# AltiumSTM32_Schematic.net
KiCad netlist of a schematic drawn in Altium Designer
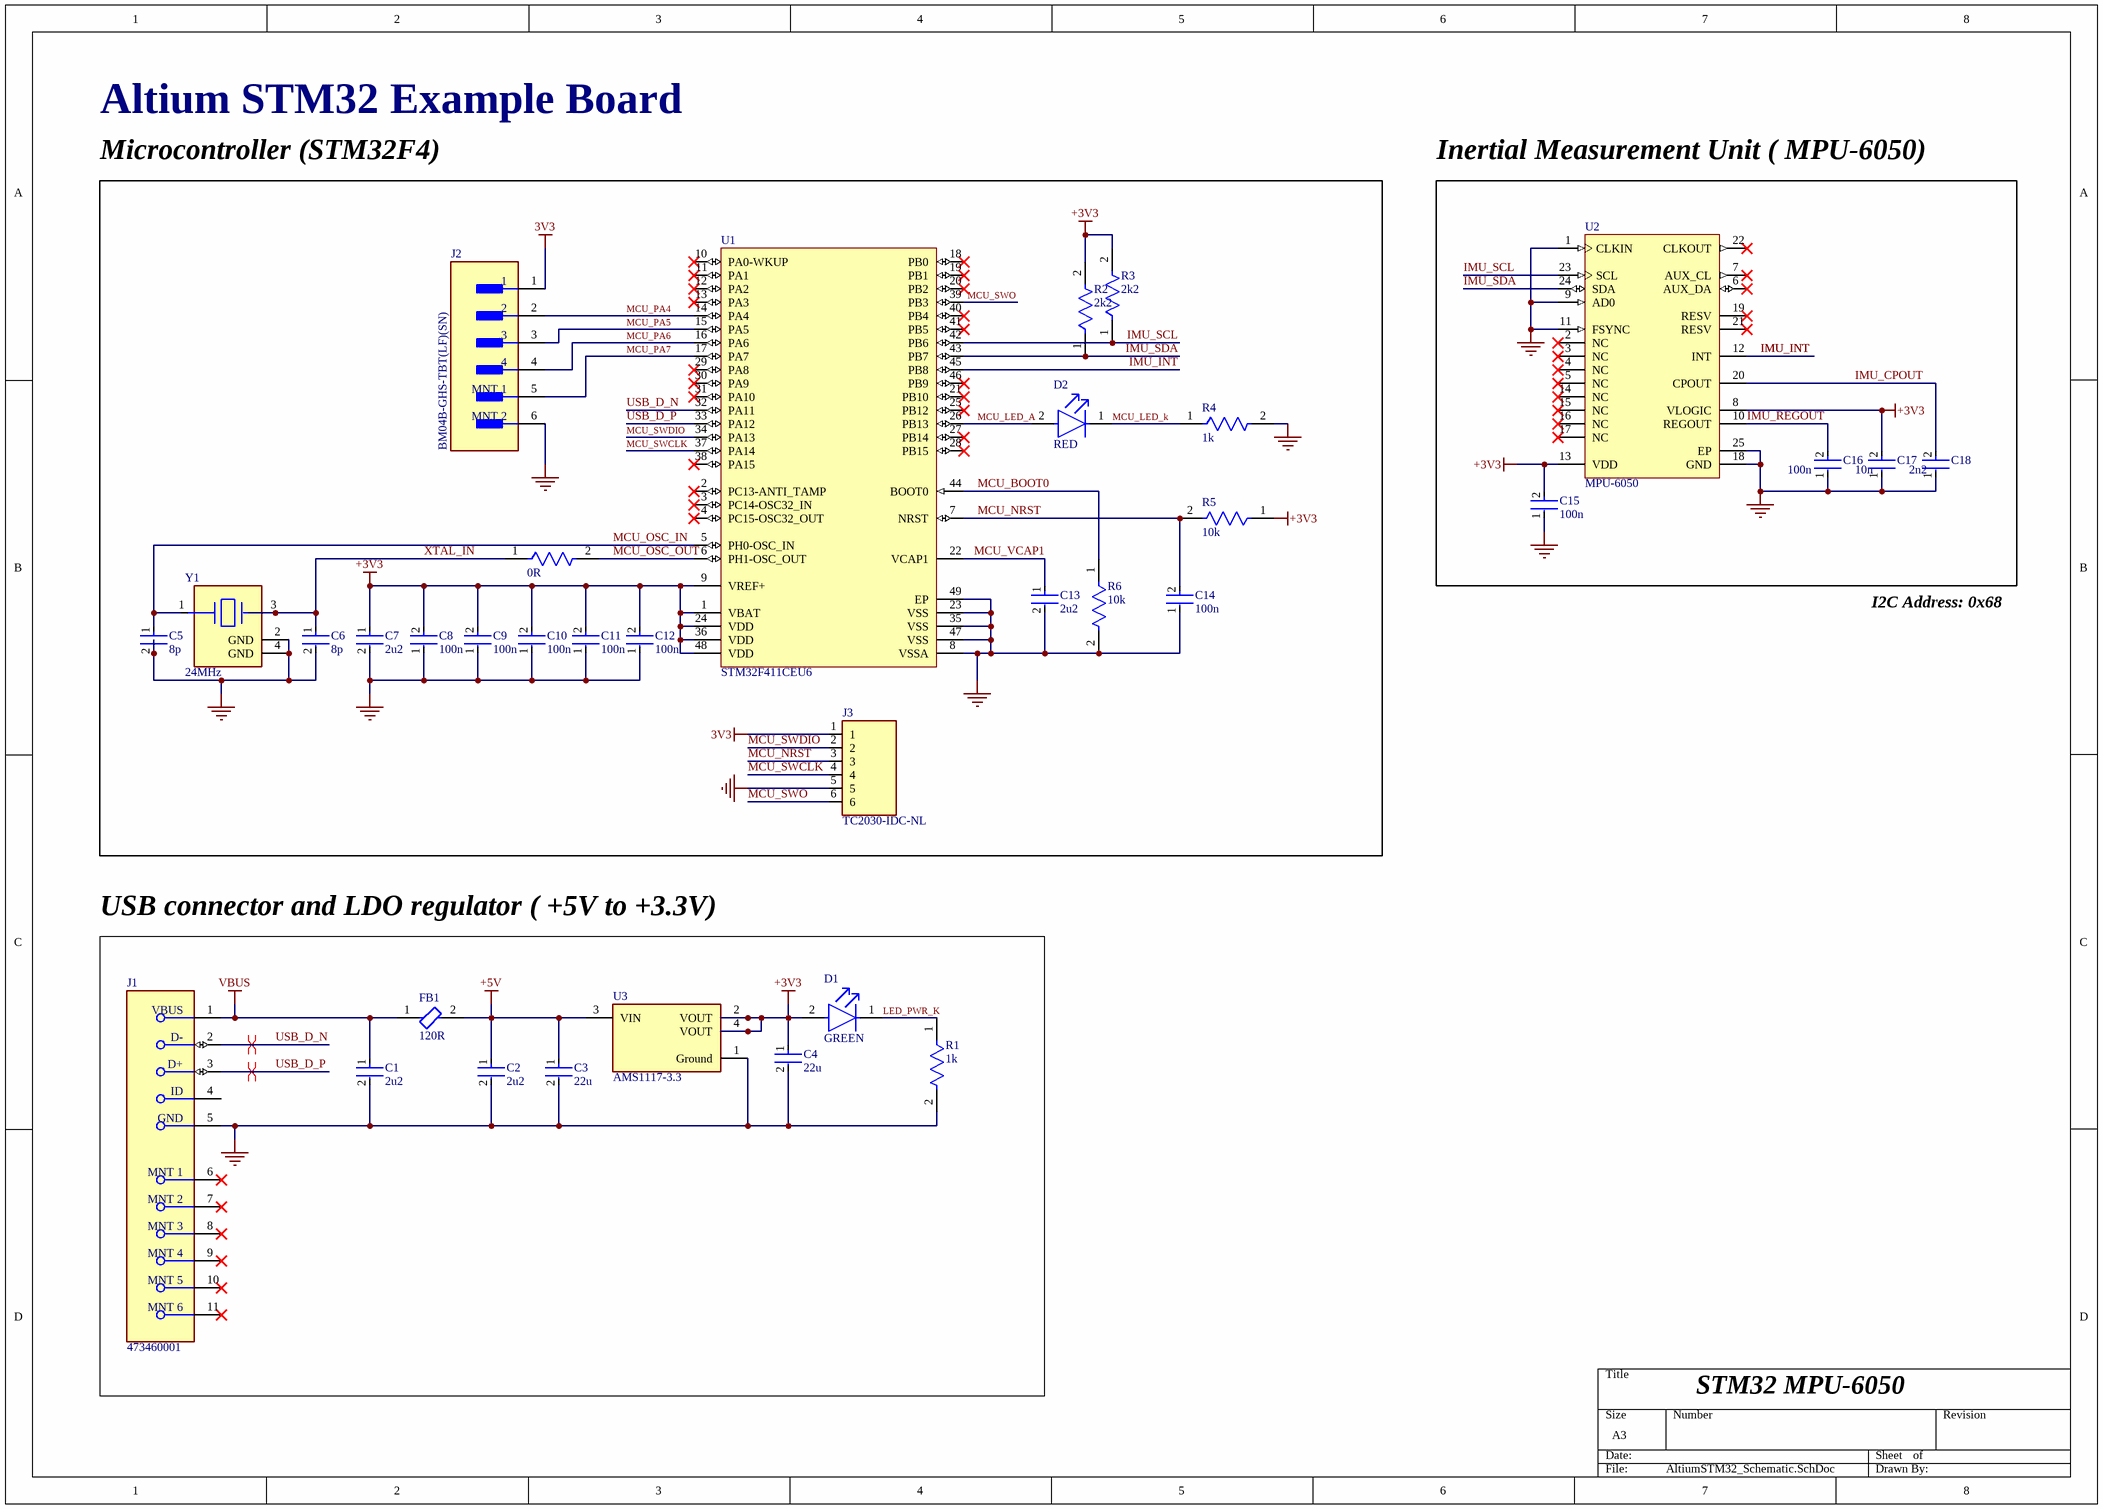
[diagram p0: AltiumSTM32_Schematic.SchDoc]

(export (version "E")
  (design (tool "Eeschema 10.0.6"))
  (components
    (comp (ref "C1")
      (value "2u2")
      (footprint "FP-CC0603-DA-MFG")
      (description "CAP CER 2.2UF 16V X7R 0603")
      (fields (field (name "VOLTAGE") "16 V") (field (name "MANUFACTURER") "YAGEO"))
      (libsource (lib "Altium Content Vault") (part "11868f565c42a9108669ba33697ecf6"))
    )
    (comp (ref "C2")
      (value "2u2")
      (footprint "FP-CC0603-DA-MFG")
      (description "CAP CER 2.2UF 16V X7R 0603")
      (fields (field (name "VOLTAGE") "16 V") (field (name "MANUFACTURER") "YAGEO"))
      (libsource (lib "Altium Content Vault") (part "11868f565c42a9108669ba33697ecf6"))
    )
    (comp (ref "C3")
      (value "22u")
      (footprint "FP-GRT21B-0_2-MFG")
      (description "Multi-Layer Ceramic Capacitor 22uF 16V X5R ±20% 0805 Emboss T/R")
      (fields (field (name "TOLERANCE") "20%"))
      (libsource (lib "Altium Content Vault") (part "02cd4be3c70576c341d710602a673aa"))
    )
    (comp (ref "C4")
      (value "22u")
      (footprint "FP-GRT21B-0_2-MFG")
      (description "Multi-Layer Ceramic Capacitor 22uF 16V X5R ±20% 0805 Emboss T/R")
      (fields (field (name "TOLERANCE") "20%"))
      (libsource (lib "Altium Content Vault") (part "02cd4be3c70576c341d710602a673aa"))
    )
    (comp (ref "C5")
      (value "8p")
      (footprint "FP-CC0402-MFG")
      (description "CAP CER 8PF 50V NPO 0402")
      (fields
        (field (name "TOLERANCE") "0.1pF")
        (field (name "MANUFACTURER PART NUMBER") "CC0402BRNPO9BN8R0")
      )
      (libsource (lib "Altium Content Vault") (part "11868f565c42a9108669ba33697ecf6"))
    )
    (comp (ref "C6")
      (value "8p")
      (footprint "FP-CC0402-MFG")
      (description "CAP CER 8PF 50V NPO 0402")
      (fields
        (field (name "TOLERANCE") "0.1pF")
        (field (name "MANUFACTURER PART NUMBER") "CC0402BRNPO9BN8R0")
      )
      (libsource (lib "Altium Content Vault") (part "11868f565c42a9108669ba33697ecf6"))
    )
    (comp (ref "C7")
      (value "2u2")
      (footprint "FP-CC0603-DA-MFG")
      (description "CAP CER 2.2UF 16V X7R 0603")
      (fields (field (name "VOLTAGE") "16 V") (field (name "MANUFACTURER") "YAGEO"))
      (libsource (lib "Altium Content Vault") (part "11868f565c42a9108669ba33697ecf6"))
    )
    (comp (ref "C8")
      (value "100n")
      (footprint "FP-CC0402-0_05-0_55-L2_0-MFG")
      (description "CAP CER 0.1UF 16V X7R 0402")
      (fields (field (name "TOLERANCE") "5%"))
      (libsource (lib "Altium Content Vault") (part "236180d848d6139a670b325ea6854c9"))
    )
    (comp (ref "C9")
      (value "100n")
      (footprint "FP-CC0402-0_05-0_55-L2_0-MFG")
      (description "CAP CER 0.1UF 16V X7R 0402")
      (fields (field (name "TOLERANCE") "5%"))
      (libsource (lib "Altium Content Vault") (part "236180d848d6139a670b325ea6854c9"))
    )
    (comp (ref "C10")
      (value "100n")
      (footprint "FP-CC0402-0_05-0_55-L2_0-MFG")
      (description "CAP CER 0.1UF 16V X7R 0402")
      (fields (field (name "TOLERANCE") "5%"))
      (libsource (lib "Altium Content Vault") (part "236180d848d6139a670b325ea6854c9"))
    )
    (comp (ref "C11")
      (value "100n")
      (footprint "FP-CC0402-0_05-0_55-L2_0-MFG")
      (description "CAP CER 0.1UF 16V X7R 0402")
      (fields (field (name "TOLERANCE") "5%"))
      (libsource (lib "Altium Content Vault") (part "236180d848d6139a670b325ea6854c9"))
    )
    (comp (ref "C12")
      (value "100n")
      (footprint "FP-CC0402-0_05-0_55-L2_0-MFG")
      (description "CAP CER 0.1UF 16V X7R 0402")
      (fields (field (name "TOLERANCE") "5%"))
      (libsource (lib "Altium Content Vault") (part "236180d848d6139a670b325ea6854c9"))
    )
    (comp (ref "C13")
      (value "2u2")
      (footprint "FP-CC0603-DA-MFG")
      (description "CAP CER 2.2UF 16V X7R 0603")
      (fields (field (name "VOLTAGE") "16 V") (field (name "MANUFACTURER") "YAGEO"))
      (libsource (lib "Altium Content Vault") (part "11868f565c42a9108669ba33697ecf6"))
    )
    (comp (ref "C14")
      (value "100n")
      (footprint "FP-CC0402-0_05-0_55-L2_0-MFG")
      (description "CAP CER 0.1UF 16V X7R 0402")
      (fields (field (name "TOLERANCE") "5%"))
      (libsource (lib "Altium Content Vault") (part "236180d848d6139a670b325ea6854c9"))
    )
    (comp (ref "C15")
      (value "100n")
      (footprint "FP-CC0402-0_05-0_55-L2_0-MFG")
      (description "CAP CER 0.1UF 16V X7R 0402")
      (fields (field (name "TOLERANCE") "5%"))
      (libsource (lib "Altium Content Vault") (part "236180d848d6139a670b325ea6854c9"))
    )
    (comp (ref "C16")
      (value "100n")
      (footprint "FP-CC0402-0_05-0_55-L2_0-MFG")
      (description "CAP CER 0.1UF 16V X7R 0402")
      (fields (field (name "TOLERANCE") "5%"))
      (libsource (lib "Altium Content Vault") (part "236180d848d6139a670b325ea6854c9"))
    )
    (comp (ref "C17")
      (value "10n")
      (footprint "FP-CC0402-0_05-0_55-L2_0-MFG")
      (description "CAP CER 0.1UF 16V X7R 0402")
      (fields (field (name "TOLERANCE") "5%"))
      (libsource (lib "Altium Content Vault") (part "236180d848d6139a670b325ea6854c9"))
    )
    (comp (ref "C18")
      (value "2n2")
      (footprint "FP-CC0402-0_05-0_55-L2_0-MFG")
      (description "CAP CER 0.1UF 16V X7R 0402")
      (fields (field (name "TOLERANCE") "5%"))
      (libsource (lib "Altium Content Vault") (part "236180d848d6139a670b325ea6854c9"))
    )
    (comp (ref "D1")
      (value "GREEN")
      (footprint "FP-SML-P1-MFG")
      (description "LED GREEN CLEAR 1006 SMD")
      (fields (field (name "MANUFACTURER PART NUMBER") "SML-P13PTT86R") (field (name "MANUFACTURER") "Rohm"))
      (libsource (lib "Altium Content Vault") (part "8706943c75ba83719d021d2fdc84c58"))
    )
    (comp (ref "D2")
      (value "RED")
      (footprint "FP-SML-P1-MFG")
      (description "LED RED CLEAR 0402 SMD")
      (fields
        (field (name "OCTOPART") "https://octopart.com/sml-p12vtt86r-rohm-34112315")
        (field (name "MANUFACTURER") "Rohm")
      )
      (libsource (lib "Altium Content Vault") (part "8706943c75ba83719d021d2fdc84c58"))
    )
    (comp (ref "FB1")
      (value "120R")
      (footprint "FP-MPZ1608-0_6-IPC_A")
      (description "FERRITE BEAD 120 OHM 0603 1LN")
      (fields (field (name "TOLERANCE") "25%"))
      (libsource (lib "Altium Content Vault") (part "5f30dd21d616792df468990f7003faa"))
    )
    (comp (ref "J1")
      (value "473460001")
      (footprint "FP-473460001-MFG")
      (description "CONN RCPT USB2.0 MICRO B SMD R/A")
      (fields
        (field (name "OCTOPART") "https://octopart.com/47346-0001-molex-7164928")
        (field (name "MANUFACTURER") "Molex")
      )
      (libsource (lib "Altium Content Vault") (part "53ae1f1d9b557310b43ca686e5bb76a"))
    )
    (comp (ref "J2")
      (value "BM04B-GHS-TBT(LF)(SN)")
      (footprint "FP-BM04B-GHS-TBT_LF_SN-MFG")
      (description "CONN HEADER SMD 4POS 1.25MM")
      (libsource (lib "Altium Content Vault") (part "8e3688c4b118bffc0dd9b7401e414ba"))
    )
    (comp (ref "J3")
      (value "TC2030-IDC-NL")
      (footprint "TC2030-IDC-NL")
      (description "CABLE ADAPTER 6 POS")
      (libsource (lib "AltiumSTM32_PCB") (part "CMP-003-000003-1"))
    )
    (comp (ref "R1")
      (value "1k")
      (footprint "FP-CRGCQ0402-IPC_C")
      (description "CRGCQ 0402 10K 1%")
      (fields (field (name "TOLERANCE") "0.01") (field (name "MANUFACTURER") "TE Connectivity"))
      (libsource (lib "Altium Content Vault") (part "1029c3af85768c4190bb7ad29bc67b5"))
    )
    (comp (ref "R2")
      (value "2k2")
      (footprint "FP-CRGCQ0402-IPC_C")
      (description "CRGCQ 0402 10K 1%")
      (fields (field (name "TOLERANCE") "0.01") (field (name "MANUFACTURER") "TE Connectivity"))
      (libsource (lib "Altium Content Vault") (part "1029c3af85768c4190bb7ad29bc67b5"))
    )
    (comp (ref "R3")
      (value "2k2")
      (footprint "FP-CRGCQ0402-IPC_C")
      (description "CRGCQ 0402 10K 1%")
      (fields (field (name "TOLERANCE") "0.01") (field (name "MANUFACTURER") "TE Connectivity"))
      (libsource (lib "Altium Content Vault") (part "1029c3af85768c4190bb7ad29bc67b5"))
    )
    (comp (ref "R4")
      (value "1k")
      (footprint "FP-CRGCQ0402-IPC_C")
      (description "CRGCQ 0402 10K 1%")
      (fields (field (name "TOLERANCE") "0.01") (field (name "MANUFACTURER") "TE Connectivity"))
      (libsource (lib "Altium Content Vault") (part "1029c3af85768c4190bb7ad29bc67b5"))
    )
    (comp (ref "R5")
      (value "10k")
      (footprint "FP-CRGCQ0402-IPC_C")
      (description "CRGCQ 0402 10K 1%")
      (fields (field (name "TOLERANCE") "0.01") (field (name "MANUFACTURER") "TE Connectivity"))
      (libsource (lib "Altium Content Vault") (part "1029c3af85768c4190bb7ad29bc67b5"))
    )
    (comp (ref "R6")
      (value "10k")
      (footprint "FP-CRGCQ0402-IPC_C")
      (description "CRGCQ 0402 10K 1%")
      (fields (field (name "TOLERANCE") "0.01") (field (name "MANUFACTURER") "TE Connectivity"))
      (libsource (lib "Altium Content Vault") (part "1029c3af85768c4190bb7ad29bc67b5"))
    )
    (comp (ref "R7")
      (value "0R")
      (footprint "FP-CRGCQ0402-IPC_C")
      (description "CRGCQ 0402 10K 1%")
      (fields (field (name "TOLERANCE") "0.01") (field (name "MANUFACTURER") "TE Connectivity"))
      (libsource (lib "Altium Content Vault") (part "1029c3af85768c4190bb7ad29bc67b5"))
    )
    (comp (ref "U1")
      (value "STM32F411CEU6")
      (footprint "STM-UFQFPN48_L")
      (libsource (lib "Altium Content Vault") (part "MC-ARM-STM32F411-UFQFPN48"))
    )
    (comp (ref "U2")
      (value "MPU-6050")
      (footprint "IS-QFN-24_V")
      (fields (field (name "MANUFACTURER") "InvenSense"))
      (libsource (lib "Altium Content Vault") (part "IS-MPU-6050-QFN-24"))
    )
    (comp (ref "U3")
      (value "AMS1117-3.3")
      (footprint "FP-AMS1117-IPC_C")
      (description "LDO Voltage Regulators 1A, 3.3V")
      (fields
        (field (name "OCTOPART") "https://octopart.com/ams1117-3.3-advanced+monolithic+systems-25899300")
        (field (name "MANUFACTURER") "Advanced Monolithic Systems")
      )
      (libsource (lib "Altium Content Vault") (part "8bdbb5f8e77002000e30dd2845d0354"))
    )
    (comp (ref "Y1")
      (value "24MHz")
      (footprint "FP-TSX-3225-MFG")
      (description "CRYSTAL 24.0000MHZ 9PF SMD")
      (fields (field (name "TOLERANCE") "10ppm"))
      (libsource (lib "Altium Content Vault") (part "862d5228ea4a4c8f16e8fb874e464c7"))
    )
  )
  (nets
    (net (code "1") (name "+3V3") (class "Default")
      (node (ref "C10") (pin "2") (pinfunction "2_2") (pintype "passive"))
      (node (ref "C11") (pin "2") (pinfunction "2_2") (pintype "passive"))
      (node (ref "C12") (pin "2") (pinfunction "2_2") (pintype "passive"))
      (node (ref "C15") (pin "2") (pinfunction "2_2") (pintype "passive"))
      (node (ref "C17") (pin "2") (pinfunction "2_2") (pintype "passive"))
      (node (ref "C4") (pin "1") (pinfunction "1_1") (pintype "passive"))
      (node (ref "C7") (pin "1") (pinfunction "1_1") (pintype "passive"))
      (node (ref "C8") (pin "2") (pinfunction "2_2") (pintype "passive"))
      (node (ref "C9") (pin "2") (pinfunction "2_2") (pintype "passive"))
      (node (ref "D1") (pin "2") (pinfunction "A_2") (pintype "passive"))
      (node (ref "R2") (pin "2") (pinfunction "2_2") (pintype "passive"))
      (node (ref "R3") (pin "2") (pinfunction "2_2") (pintype "passive"))
      (node (ref "R5") (pin "1") (pinfunction "1_1") (pintype "passive"))
      (node (ref "U1") (pin "1") (pinfunction "VBAT_1") (pintype "power_in"))
      (node (ref "U1") (pin "24") (pinfunction "VDD_24") (pintype "power_in"))
      (node (ref "U1") (pin "36") (pinfunction "VDD_36") (pintype "power_in"))
      (node (ref "U1") (pin "48") (pinfunction "VDD_48") (pintype "power_in"))
      (node (ref "U1") (pin "9") (pinfunction "VREF+_9") (pintype "power_in"))
      (node (ref "U2") (pin "13") (pinfunction "VDD_13") (pintype "power_in"))
      (node (ref "U2") (pin "8") (pinfunction "VLOGIC_8") (pintype "power_in"))
      (node (ref "U3") (pin "2") (pinfunction "VOUT_2") (pintype "passive"))
      (node (ref "U3") (pin "4") (pinfunction "VOUT_4") (pintype "passive"))
    )
    (net (code "2") (name "+5V") (class "Default")
      (node (ref "C2") (pin "1") (pinfunction "1_1") (pintype "passive"))
      (node (ref "C3") (pin "1") (pinfunction "1_1") (pintype "passive"))
      (node (ref "FB1") (pin "2") (pinfunction "2_2") (pintype "passive"))
      (node (ref "U3") (pin "3") (pinfunction "VIN_3") (pintype "power_in"))
    )
    (net (code "3") (name "/IMU_CPOUT") (class "Default")
      (node (ref "C18") (pin "2") (pinfunction "2_2") (pintype "passive"))
      (node (ref "U2") (pin "20") (pinfunction "CPOUT_20") (pintype "passive"))
    )
    (net (code "4") (name "/IMU_INT") (class "Default")
      (node (ref "U1") (pin "45") (pinfunction "PB8_45") (pintype "bidirectional"))
      (node (ref "U2") (pin "12") (pinfunction "INT_12") (pintype "open_collector"))
    )
    (net (code "5") (name "/IMU_REGOUT") (class "Default")
      (node (ref "C16") (pin "2") (pinfunction "2_2") (pintype "passive"))
      (node (ref "U2") (pin "10") (pinfunction "REGOUT_10") (pintype "passive"))
    )
    (net (code "6") (name "/IMU_SCL") (class "Default")
      (node (ref "R3") (pin "1") (pinfunction "1_1") (pintype "passive"))
      (node (ref "U1") (pin "42") (pinfunction "PB6_42") (pintype "bidirectional"))
      (node (ref "U2") (pin "23") (pinfunction "SCL_23") (pintype "input"))
    )
    (net (code "7") (name "/IMU_SDA") (class "Default")
      (node (ref "R2") (pin "1") (pinfunction "1_1") (pintype "passive"))
      (node (ref "U1") (pin "43") (pinfunction "PB7_43") (pintype "bidirectional"))
      (node (ref "U2") (pin "24") (pinfunction "SDA_24") (pintype "bidirectional"))
    )
    (net (code "8") (name "/LED_PWR_K") (class "Default")
      (node (ref "D1") (pin "1") (pinfunction "C_1") (pintype "passive"))
      (node (ref "R1") (pin "1") (pinfunction "1_1") (pintype "passive"))
    )
    (net (code "9") (name "/MCU_BOOT0") (class "Default")
      (node (ref "R6") (pin "1") (pinfunction "1_1") (pintype "passive"))
      (node (ref "U1") (pin "44") (pinfunction "BOOT0_44") (pintype "input"))
    )
    (net (code "10") (name "/MCU_LED_A") (class "Default")
      (node (ref "D2") (pin "2") (pinfunction "A_2") (pintype "passive"))
      (node (ref "U1") (pin "26") (pinfunction "PB13_26") (pintype "bidirectional"))
    )
    (net (code "11") (name "/MCU_LED_k") (class "Default")
      (node (ref "D2") (pin "1") (pinfunction "C_1") (pintype "passive"))
      (node (ref "R4") (pin "1") (pinfunction "1_1") (pintype "passive"))
    )
    (net (code "12") (name "/MCU_NRST") (class "Default")
      (node (ref "C14") (pin "2") (pinfunction "2_2") (pintype "passive"))
      (node (ref "J3") (pin "3") (pinfunction "3_3") (pintype "passive"))
      (node (ref "R5") (pin "2") (pinfunction "2_2") (pintype "passive"))
      (node (ref "U1") (pin "7") (pinfunction "NRST_7") (pintype "bidirectional"))
    )
    (net (code "13") (name "/MCU_OSC_IN") (class "Default")
      (node (ref "C5") (pin "1") (pinfunction "1_1") (pintype "passive"))
      (node (ref "U1") (pin "5") (pinfunction "PH0-OSC_IN_5") (pintype "bidirectional"))
      (node (ref "Y1") (pin "1") (pinfunction "1_1") (pintype "passive"))
    )
    (net (code "14") (name "/MCU_OSC_OUT") (class "Default")
      (node (ref "R7") (pin "2") (pinfunction "2_2") (pintype "passive"))
      (node (ref "U1") (pin "6") (pinfunction "PH1-OSC_OUT_6") (pintype "bidirectional"))
    )
    (net (code "15") (name "/MCU_PA4") (class "Default")
      (node (ref "J2") (pin "2") (pinfunction "2_2") (pintype "passive"))
      (node (ref "U1") (pin "14") (pinfunction "PA4_14") (pintype "bidirectional"))
    )
    (net (code "16") (name "/MCU_PA5") (class "Default")
      (node (ref "J2") (pin "3") (pinfunction "3_3") (pintype "passive"))
      (node (ref "U1") (pin "15") (pinfunction "PA5_15") (pintype "bidirectional"))
    )
    (net (code "17") (name "/MCU_PA6") (class "Default")
      (node (ref "J2") (pin "4") (pinfunction "4_4") (pintype "passive"))
      (node (ref "U1") (pin "16") (pinfunction "PA6_16") (pintype "bidirectional"))
    )
    (net (code "18") (name "/MCU_PA7") (class "Default")
      (node (ref "J2") (pin "5") (pinfunction "MNT_1_5") (pintype "passive"))
      (node (ref "U1") (pin "17") (pinfunction "PA7_17") (pintype "bidirectional"))
    )
    (net (code "19") (name "/MCU_SWCLK") (class "Default")
      (node (ref "J3") (pin "4") (pinfunction "4_4") (pintype "passive"))
      (node (ref "U1") (pin "37") (pinfunction "PA14_37") (pintype "bidirectional"))
    )
    (net (code "20") (name "/MCU_SWDIO") (class "Default")
      (node (ref "J3") (pin "2") (pinfunction "2_2") (pintype "passive"))
      (node (ref "U1") (pin "34") (pinfunction "PA13_34") (pintype "bidirectional"))
    )
    (net (code "21") (name "/MCU_SWO") (class "Default")
      (node (ref "J3") (pin "6") (pinfunction "6_6") (pintype "passive"))
      (node (ref "U1") (pin "39") (pinfunction "PB3_39") (pintype "bidirectional"))
    )
    (net (code "22") (name "/MCU_VCAP1") (class "Default")
      (node (ref "C13") (pin "1") (pinfunction "1_1") (pintype "passive"))
      (node (ref "U1") (pin "22") (pinfunction "VCAP1_22") (pintype "passive"))
    )
    (net (code "23") (name "/USB_D_N") (class "Default")
      (node (ref "J1") (pin "2") (pinfunction "D-_2") (pintype "bidirectional"))
      (node (ref "U1") (pin "32") (pinfunction "PA11_32") (pintype "bidirectional"))
    )
    (net (code "24") (name "/USB_D_P") (class "Default")
      (node (ref "J1") (pin "3") (pinfunction "D+_3") (pintype "bidirectional"))
      (node (ref "U1") (pin "33") (pinfunction "PA12_33") (pintype "bidirectional"))
    )
    (net (code "25") (name "/XTAL_IN") (class "Default")
      (node (ref "C6") (pin "1") (pinfunction "1_1") (pintype "passive"))
      (node (ref "R7") (pin "1") (pinfunction "1_1") (pintype "passive"))
      (node (ref "Y1") (pin "3") (pinfunction "3_3") (pintype "passive"))
    )
    (net (code "26") (name "3V3") (class "Default")
      (node (ref "J2") (pin "1") (pinfunction "1_1") (pintype "passive"))
      (node (ref "J3") (pin "1") (pinfunction "1_1") (pintype "passive"))
    )
    (net (code "27") (name "GND") (class "Default")
      (node (ref "C1") (pin "2") (pinfunction "2_2") (pintype "passive"))
      (node (ref "C10") (pin "1") (pinfunction "1_1") (pintype "passive"))
      (node (ref "C11") (pin "1") (pinfunction "1_1") (pintype "passive"))
      (node (ref "C12") (pin "1") (pinfunction "1_1") (pintype "passive"))
      (node (ref "C13") (pin "2") (pinfunction "2_2") (pintype "passive"))
      (node (ref "C14") (pin "1") (pinfunction "1_1") (pintype "passive"))
      (node (ref "C15") (pin "1") (pinfunction "1_1") (pintype "passive"))
      (node (ref "C16") (pin "1") (pinfunction "1_1") (pintype "passive"))
      (node (ref "C17") (pin "1") (pinfunction "1_1") (pintype "passive"))
      (node (ref "C18") (pin "1") (pinfunction "1_1") (pintype "passive"))
      (node (ref "C2") (pin "2") (pinfunction "2_2") (pintype "passive"))
      (node (ref "C3") (pin "2") (pinfunction "2_2") (pintype "passive"))
      (node (ref "C4") (pin "2") (pinfunction "2_2") (pintype "passive"))
      (node (ref "C5") (pin "2") (pinfunction "2_2") (pintype "passive"))
      (node (ref "C6") (pin "2") (pinfunction "2_2") (pintype "passive"))
      (node (ref "C7") (pin "2") (pinfunction "2_2") (pintype "passive"))
      (node (ref "C8") (pin "1") (pinfunction "1_1") (pintype "passive"))
      (node (ref "C9") (pin "1") (pinfunction "1_1") (pintype "passive"))
      (node (ref "J1") (pin "5") (pinfunction "GND_5") (pintype "power_in"))
      (node (ref "J2") (pin "6") (pinfunction "MNT_2_6") (pintype "passive"))
      (node (ref "J3") (pin "5") (pinfunction "5_5") (pintype "passive"))
      (node (ref "R1") (pin "2") (pinfunction "2_2") (pintype "passive"))
      (node (ref "R4") (pin "2") (pinfunction "2_2") (pintype "passive"))
      (node (ref "R6") (pin "2") (pinfunction "2_2") (pintype "passive"))
      (node (ref "U1") (pin "23") (pinfunction "VSS_23") (pintype "power_in"))
      (node (ref "U1") (pin "35") (pinfunction "VSS_35") (pintype "power_in"))
      (node (ref "U1") (pin "47") (pinfunction "VSS_47") (pintype "power_in"))
      (node (ref "U1") (pin "49") (pinfunction "EP_49") (pintype "power_in"))
      (node (ref "U1") (pin "8") (pinfunction "VSSA_8") (pintype "power_in"))
      (node (ref "U2") (pin "1") (pinfunction "CLKIN_1") (pintype "input"))
      (node (ref "U2") (pin "11") (pinfunction "FSYNC_11") (pintype "input"))
      (node (ref "U2") (pin "18") (pinfunction "GND_18") (pintype "power_in"))
      (node (ref "U2") (pin "25") (pinfunction "EP_25") (pintype "power_in"))
      (node (ref "U2") (pin "9") (pinfunction "AD0_9") (pintype "input"))
      (node (ref "U3") (pin "1") (pinfunction "Ground_1") (pintype "power_in"))
      (node (ref "Y1") (pin "2") (pinfunction "GND_2") (pintype "power_in"))
      (node (ref "Y1") (pin "4") (pinfunction "GND_4") (pintype "power_in"))
    )
    (net (code "28") (name "VBUS") (class "Default")
      (node (ref "C1") (pin "1") (pinfunction "1_1") (pintype "passive"))
      (node (ref "FB1") (pin "1") (pinfunction "1_1") (pintype "passive"))
      (node (ref "J1") (pin "1") (pinfunction "VBUS_1") (pintype "power_in"))
    )
    (net (code "29") (name "unconnected-(J1-ID-Pad4)") (class "Default")
      (node (ref "J1") (pin "4") (pinfunction "ID_4") (pintype "passive"))
    )
    (net (code "30") (name "unconnected-(J1-MNT_1-Pad6)") (class "Default")
      (node (ref "J1") (pin "6") (pinfunction "MNT_1_6") (pintype "passive+no_connect"))
    )
    (net (code "31") (name "unconnected-(J1-MNT_2-Pad7)") (class "Default")
      (node (ref "J1") (pin "7") (pinfunction "MNT_2_7") (pintype "passive+no_connect"))
    )
    (net (code "32") (name "unconnected-(J1-MNT_3-Pad8)") (class "Default")
      (node (ref "J1") (pin "8") (pinfunction "MNT_3_8") (pintype "passive+no_connect"))
    )
    (net (code "33") (name "unconnected-(J1-MNT_4-Pad9)") (class "Default")
      (node (ref "J1") (pin "9") (pinfunction "MNT_4_9") (pintype "passive+no_connect"))
    )
    (net (code "34") (name "unconnected-(J1-MNT_5-Pad10)") (class "Default")
      (node (ref "J1") (pin "10") (pinfunction "MNT_5_10") (pintype "passive+no_connect"))
    )
    (net (code "35") (name "unconnected-(J1-MNT_6-Pad11)") (class "Default")
      (node (ref "J1") (pin "11") (pinfunction "MNT_6_11") (pintype "passive+no_connect"))
    )
    (net (code "36") (name "unconnected-(U1-PA0-WKUP-Pad10)") (class "Default")
      (node (ref "U1") (pin "10") (pinfunction "PA0-WKUP_10") (pintype "bidirectional+no_connect"))
    )
    (net (code "37") (name "unconnected-(U1-PA1-Pad11)") (class "Default")
      (node (ref "U1") (pin "11") (pinfunction "PA1_11") (pintype "bidirectional+no_connect"))
    )
    (net (code "38") (name "unconnected-(U1-PA2-Pad12)") (class "Default")
      (node (ref "U1") (pin "12") (pinfunction "PA2_12") (pintype "bidirectional+no_connect"))
    )
    (net (code "39") (name "unconnected-(U1-PA3-Pad13)") (class "Default")
      (node (ref "U1") (pin "13") (pinfunction "PA3_13") (pintype "bidirectional+no_connect"))
    )
    (net (code "40") (name "unconnected-(U1-PA8-Pad29)") (class "Default")
      (node (ref "U1") (pin "29") (pinfunction "PA8_29") (pintype "bidirectional+no_connect"))
    )
    (net (code "41") (name "unconnected-(U1-PA9-Pad30)") (class "Default")
      (node (ref "U1") (pin "30") (pinfunction "PA9_30") (pintype "bidirectional+no_connect"))
    )
    (net (code "42") (name "unconnected-(U1-PA10-Pad31)") (class "Default")
      (node (ref "U1") (pin "31") (pinfunction "PA10_31") (pintype "bidirectional+no_connect"))
    )
    (net (code "43") (name "unconnected-(U1-PA15-Pad38)") (class "Default")
      (node (ref "U1") (pin "38") (pinfunction "PA15_38") (pintype "bidirectional+no_connect"))
    )
    (net (code "44") (name "unconnected-(U1-PB0-Pad18)") (class "Default")
      (node (ref "U1") (pin "18") (pinfunction "PB0_18") (pintype "bidirectional+no_connect"))
    )
    (net (code "45") (name "unconnected-(U1-PB1-Pad19)") (class "Default")
      (node (ref "U1") (pin "19") (pinfunction "PB1_19") (pintype "bidirectional+no_connect"))
    )
    (net (code "46") (name "unconnected-(U1-PB2-Pad20)") (class "Default")
      (node (ref "U1") (pin "20") (pinfunction "PB2_20") (pintype "bidirectional+no_connect"))
    )
    (net (code "47") (name "unconnected-(U1-PB4-Pad40)") (class "Default")
      (node (ref "U1") (pin "40") (pinfunction "PB4_40") (pintype "bidirectional+no_connect"))
    )
    (net (code "48") (name "unconnected-(U1-PB5-Pad41)") (class "Default")
      (node (ref "U1") (pin "41") (pinfunction "PB5_41") (pintype "bidirectional+no_connect"))
    )
    (net (code "49") (name "unconnected-(U1-PB9-Pad46)") (class "Default")
      (node (ref "U1") (pin "46") (pinfunction "PB9_46") (pintype "bidirectional+no_connect"))
    )
    (net (code "50") (name "unconnected-(U1-PB10-Pad21)") (class "Default")
      (node (ref "U1") (pin "21") (pinfunction "PB10_21") (pintype "bidirectional+no_connect"))
    )
    (net (code "51") (name "unconnected-(U1-PB12-Pad25)") (class "Default")
      (node (ref "U1") (pin "25") (pinfunction "PB12_25") (pintype "bidirectional+no_connect"))
    )
    (net (code "52") (name "unconnected-(U1-PB14-Pad27)") (class "Default")
      (node (ref "U1") (pin "27") (pinfunction "PB14_27") (pintype "bidirectional+no_connect"))
    )
    (net (code "53") (name "unconnected-(U1-PB15-Pad28)") (class "Default")
      (node (ref "U1") (pin "28") (pinfunction "PB15_28") (pintype "bidirectional+no_connect"))
    )
    (net (code "54") (name "unconnected-(U1-PC13-ANTI_TAMP-Pad2)") (class "Default")
      (node (ref "U1") (pin "2") (pinfunction "PC13-ANTI_TAMP_2") (pintype "bidirectional+no_connect"))
    )
    (net (code "55") (name "unconnected-(U1-PC14-OSC32_IN-Pad3)") (class "Default")
      (node (ref "U1") (pin "3") (pinfunction "PC14-OSC32_IN_3") (pintype "bidirectional+no_connect"))
    )
    (net (code "56") (name "unconnected-(U1-PC15-OSC32_OUT-Pad4)") (class "Default")
      (node (ref "U1") (pin "4") (pinfunction "PC15-OSC32_OUT_4") (pintype "bidirectional+no_connect"))
    )
    (net (code "57") (name "unconnected-(U2-AUX_CL-Pad7)") (class "Default")
      (node (ref "U2") (pin "7") (pinfunction "AUX_CL_7") (pintype "output+no_connect"))
    )
    (net (code "58") (name "unconnected-(U2-AUX_DA-Pad6)") (class "Default")
      (node (ref "U2") (pin "6") (pinfunction "AUX_DA_6") (pintype "bidirectional+no_connect"))
    )
    (net (code "59") (name "unconnected-(U2-CLKOUT-Pad22)") (class "Default")
      (node (ref "U2") (pin "22") (pinfunction "CLKOUT_22") (pintype "output+no_connect"))
    )
    (net (code "60") (name "unconnected-(U2-NC-Pad2)") (class "Default")
      (node (ref "U2") (pin "2") (pinfunction "NC_2") (pintype "passive+no_connect"))
    )
    (net (code "61") (name "unconnected-(U2-NC-Pad3)") (class "Default")
      (node (ref "U2") (pin "3") (pinfunction "NC_3") (pintype "passive+no_connect"))
    )
    (net (code "62") (name "unconnected-(U2-NC-Pad4)") (class "Default")
      (node (ref "U2") (pin "4") (pinfunction "NC_4") (pintype "passive+no_connect"))
    )
    (net (code "63") (name "unconnected-(U2-NC-Pad5)") (class "Default")
      (node (ref "U2") (pin "5") (pinfunction "NC_5") (pintype "passive+no_connect"))
    )
    (net (code "64") (name "unconnected-(U2-NC-Pad14)") (class "Default")
      (node (ref "U2") (pin "14") (pinfunction "NC_14") (pintype "passive+no_connect"))
    )
    (net (code "65") (name "unconnected-(U2-NC-Pad15)") (class "Default")
      (node (ref "U2") (pin "15") (pinfunction "NC_15") (pintype "passive+no_connect"))
    )
    (net (code "66") (name "unconnected-(U2-NC-Pad16)") (class "Default")
      (node (ref "U2") (pin "16") (pinfunction "NC_16") (pintype "passive+no_connect"))
    )
    (net (code "67") (name "unconnected-(U2-NC-Pad17)") (class "Default")
      (node (ref "U2") (pin "17") (pinfunction "NC_17") (pintype "passive+no_connect"))
    )
    (net (code "68") (name "unconnected-(U2-RESV-Pad19)") (class "Default")
      (node (ref "U2") (pin "19") (pinfunction "RESV_19") (pintype "passive+no_connect"))
    )
    (net (code "69") (name "unconnected-(U2-RESV-Pad21)") (class "Default")
      (node (ref "U2") (pin "21") (pinfunction "RESV_21") (pintype "passive+no_connect"))
    )
  )
)
